# Drifter.net
KiCad netlist of a schematic drawn in EAGLE
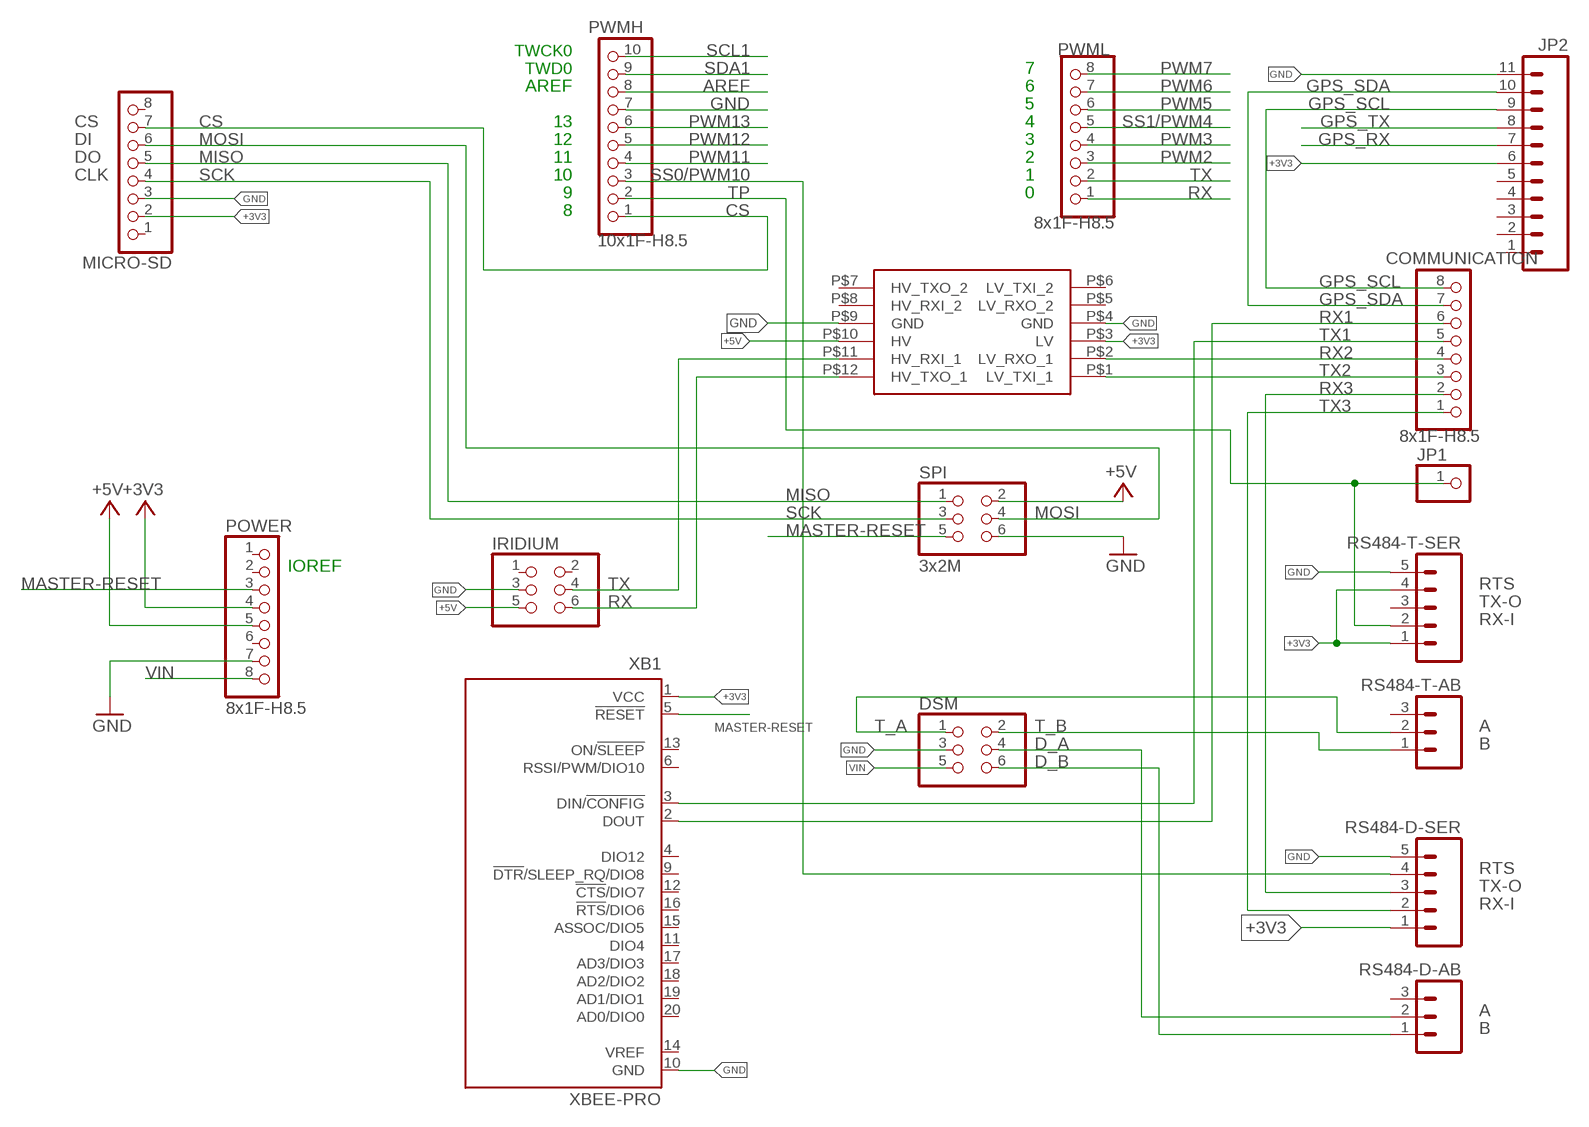
[diagram p0: schematic, sheet 1]

(export (version "E")
  (design (tool "Eeschema 10.0.6"))
  (components
    (comp (ref "COMMUNICATION")
      (value "8x1F-H8.5")
      (footprint "eagle-import:1X08")
      (libsource (lib "eagle-import") (part "PINHD-1X8"))
    )
    (comp (ref "DSM")
      (value "PINHD-2X3")
      (footprint "eagle-import:2X03")
      (libsource (lib "eagle-import") (part "pinhead_PINHD-2X3"))
    )
    (comp (ref "IRIDIUM")
      (value "PINHD-2X3")
      (footprint "eagle-import:2X03")
      (libsource (lib "eagle-import") (part "pinhead_PINHD-2X3"))
    )
    (comp (ref "JP1")
      (value "PINHD-1X1")
      (footprint "eagle-import:1X01")
      (libsource (lib "eagle-import") (part "PINHD-1X1"))
    )
    (comp (ref "JP2")
      (value "M111.27MM")
      (footprint "eagle-import:1X11-1.27MM")
      (libsource (lib "eagle-import") (part "M111.27MM"))
    )
    (comp (ref "MICRO-SD")
      (value "PINHD-1X8BIG")
      (footprint "eagle-import:1X08-BIG")
      (libsource (lib "eagle-import") (part "PINHD-1X8BIG"))
    )
    (comp (ref "POWER")
      (value "8x1F-H8.5")
      (footprint "eagle-import:1X08")
      (libsource (lib "eagle-import") (part "PINHD-1X8"))
    )
    (comp (ref "PWMH")
      (value "10x1F-H8.5")
      (footprint "eagle-import:1X10")
      (libsource (lib "eagle-import") (part "PINHD-1X10"))
    )
    (comp (ref "PWML")
      (value "8x1F-H8.5")
      (footprint "eagle-import:1X08")
      (libsource (lib "eagle-import") (part "PINHD-1X8"))
    )
    (comp (ref "RS484-D-AB")
      (value "M03PTH")
      (footprint "eagle-import:1X03")
      (libsource (lib "eagle-import") (part "M03PTH"))
    )
    (comp (ref "RS484-D-SER")
      (value "M05PTH")
      (footprint "eagle-import:1X05")
      (libsource (lib "eagle-import") (part "M05PTH"))
    )
    (comp (ref "RS484-T-AB")
      (value "M03PTH")
      (footprint "eagle-import:1X03")
      (libsource (lib "eagle-import") (part "M03PTH"))
    )
    (comp (ref "RS484-T-SER")
      (value "M05PTH")
      (footprint "eagle-import:1X05")
      (libsource (lib "eagle-import") (part "M05PTH"))
    )
    (comp (ref "SPI")
      (value "3x2M")
      (footprint "eagle-import:2X03")
      (libsource (lib "eagle-import") (part "PINHD-2X3"))
    )
    (comp (ref "U$1")
      (value "LOGIC_LEVEL_CONVERTER")
      (footprint "eagle-import:LOGIC_LEVEL_CONVERTER")
      (libsource (lib "eagle-import") (part "LOGIC_LEVEL_CONVERTER"))
    )
    (comp (ref "XB1")
      (value "XBEE-PRO")
      (footprint "eagle-import:XBEE-PRO")
      (fields (field (name "MPN") "XBP24-AWI-001"))
      (libsource (lib "eagle-import") (part "XBEE-PRO"))
    )
  )
  (nets
    (net (code "1") (name "+3V3") (class "Default")
      (node (ref "JP2") (pin "6") (pinfunction "6_6") (pintype "passive"))
      (node (ref "MICRO-SD") (pin "2") (pinfunction "2_2") (pintype "passive"))
      (node (ref "POWER") (pin "4") (pinfunction "4_4") (pintype "passive"))
      (node (ref "RS484-D-SER") (pin "1") (pinfunction "1_1") (pintype "passive"))
      (node (ref "RS484-T-SER") (pin "1") (pinfunction "1_1") (pintype "passive"))
      (node (ref "RS484-T-SER") (pin "4") (pinfunction "4_4") (pintype "passive"))
      (node (ref "U$1") (pin "P$3") (pinfunction "LV_P$3") (pintype "bidirectional"))
      (node (ref "XB1") (pin "1") (pinfunction "VCC_1") (pintype "power_in"))
    )
    (net (code "2") (name "+5V") (class "Default")
      (node (ref "IRIDIUM") (pin "5") (pinfunction "5_5") (pintype "passive"))
      (node (ref "POWER") (pin "5") (pinfunction "5_5") (pintype "passive"))
      (node (ref "SPI") (pin "2") (pinfunction "2_2") (pintype "passive"))
      (node (ref "U$1") (pin "P$10") (pinfunction "HV_P$10") (pintype "bidirectional"))
    )
    (net (code "3") (name "/AREF") (class "Default")
      (node (ref "PWMH") (pin "8") (pinfunction "8_8") (pintype "passive"))
    )
    (net (code "4") (name "/CS") (class "Default")
      (node (ref "MICRO-SD") (pin "7") (pinfunction "7_7") (pintype "passive"))
      (node (ref "PWMH") (pin "1") (pinfunction "1_1") (pintype "passive"))
    )
    (net (code "5") (name "/D_A") (class "Default")
      (node (ref "DSM") (pin "4") (pinfunction "4_4") (pintype "passive"))
      (node (ref "RS484-D-AB") (pin "2") (pinfunction "2_2") (pintype "passive"))
    )
    (net (code "6") (name "/D_B") (class "Default")
      (node (ref "DSM") (pin "6") (pinfunction "6_6") (pintype "passive"))
      (node (ref "RS484-D-AB") (pin "1") (pinfunction "1_1") (pintype "passive"))
    )
    (net (code "7") (name "/GPS_RX") (class "Default")
      (node (ref "JP2") (pin "7") (pinfunction "7_7") (pintype "passive"))
    )
    (net (code "8") (name "/GPS_SCL") (class "Default")
      (node (ref "COMMUNICATION") (pin "8") (pinfunction "8_8") (pintype "passive"))
      (node (ref "JP2") (pin "9") (pinfunction "9_9") (pintype "passive"))
    )
    (net (code "9") (name "/GPS_SDA") (class "Default")
      (node (ref "COMMUNICATION") (pin "7") (pinfunction "7_7") (pintype "passive"))
      (node (ref "JP2") (pin "10") (pinfunction "10_10") (pintype "passive"))
    )
    (net (code "10") (name "/GPS_TX") (class "Default")
      (node (ref "JP2") (pin "8") (pinfunction "8_8") (pintype "passive"))
    )
    (net (code "11") (name "/MASTER-RESET") (class "Default")
      (node (ref "POWER") (pin "3") (pinfunction "3_3") (pintype "passive"))
      (node (ref "SPI") (pin "5") (pinfunction "5_5") (pintype "passive"))
      (node (ref "XB1") (pin "5") (pinfunction "~{RESET}_5") (pintype "input"))
    )
    (net (code "12") (name "/MISO") (class "Default")
      (node (ref "MICRO-SD") (pin "5") (pinfunction "5_5") (pintype "passive"))
      (node (ref "SPI") (pin "1") (pinfunction "1_1") (pintype "passive"))
    )
    (net (code "13") (name "/MOSI") (class "Default")
      (node (ref "MICRO-SD") (pin "6") (pinfunction "6_6") (pintype "passive"))
      (node (ref "SPI") (pin "4") (pinfunction "4_4") (pintype "passive"))
    )
    (net (code "14") (name "/PWM2") (class "Default")
      (node (ref "PWML") (pin "3") (pinfunction "3_3") (pintype "passive"))
    )
    (net (code "15") (name "/PWM3") (class "Default")
      (node (ref "PWML") (pin "4") (pinfunction "4_4") (pintype "passive"))
    )
    (net (code "16") (name "/PWM5") (class "Default")
      (node (ref "PWML") (pin "6") (pinfunction "6_6") (pintype "passive"))
    )
    (net (code "17") (name "/PWM6") (class "Default")
      (node (ref "PWML") (pin "7") (pinfunction "7_7") (pintype "passive"))
    )
    (net (code "18") (name "/PWM7") (class "Default")
      (node (ref "PWML") (pin "8") (pinfunction "8_8") (pintype "passive"))
    )
    (net (code "19") (name "/PWM11") (class "Default")
      (node (ref "PWMH") (pin "4") (pinfunction "4_4") (pintype "passive"))
    )
    (net (code "20") (name "/PWM12") (class "Default")
      (node (ref "PWMH") (pin "5") (pinfunction "5_5") (pintype "passive"))
    )
    (net (code "21") (name "/PWM13") (class "Default")
      (node (ref "PWMH") (pin "6") (pinfunction "6_6") (pintype "passive"))
    )
    (net (code "22") (name "/RX") (class "Default")
      (node (ref "PWML") (pin "1") (pinfunction "1_1") (pintype "passive"))
    )
    (net (code "23") (name "/RX1") (class "Default")
      (node (ref "COMMUNICATION") (pin "6") (pinfunction "6_6") (pintype "passive"))
      (node (ref "XB1") (pin "2") (pinfunction "DOUT_2") (pintype "output"))
    )
    (net (code "24") (name "/RX2") (class "Default")
      (node (ref "COMMUNICATION") (pin "4") (pinfunction "4_4") (pintype "passive"))
      (node (ref "U$1") (pin "P$2") (pinfunction "LV_RXO_1_P$2") (pintype "bidirectional"))
    )
    (net (code "25") (name "/RX3") (class "Default")
      (node (ref "COMMUNICATION") (pin "2") (pinfunction "2_2") (pintype "passive"))
      (node (ref "RS484-D-SER") (pin "3") (pinfunction "3_3") (pintype "passive"))
    )
    (net (code "26") (name "/SCK") (class "Default")
      (node (ref "MICRO-SD") (pin "4") (pinfunction "4_4") (pintype "passive"))
      (node (ref "SPI") (pin "3") (pinfunction "3_3") (pintype "passive"))
    )
    (net (code "27") (name "/SCL1") (class "Default")
      (node (ref "PWMH") (pin "10") (pinfunction "10_10") (pintype "passive"))
    )
    (net (code "28") (name "/SDA1") (class "Default")
      (node (ref "PWMH") (pin "9") (pinfunction "9_9") (pintype "passive"))
    )
    (net (code "29") (name "/SS0{slash}PWM10") (class "Default")
      (node (ref "PWMH") (pin "3") (pinfunction "3_3") (pintype "passive"))
      (node (ref "RS484-D-SER") (pin "4") (pinfunction "4_4") (pintype "passive"))
    )
    (net (code "30") (name "/SS1{slash}PWM4") (class "Default")
      (node (ref "PWML") (pin "5") (pinfunction "5_5") (pintype "passive"))
    )
    (net (code "31") (name "/TP") (class "Default")
      (node (ref "JP1") (pin "1") (pinfunction "1_1") (pintype "passive"))
      (node (ref "PWMH") (pin "2") (pinfunction "2_2") (pintype "passive"))
      (node (ref "RS484-T-SER") (pin "2") (pinfunction "2_2") (pintype "passive"))
    )
    (net (code "32") (name "/TX") (class "Default")
      (node (ref "PWML") (pin "2") (pinfunction "2_2") (pintype "passive"))
    )
    (net (code "33") (name "/TX1") (class "Default")
      (node (ref "COMMUNICATION") (pin "5") (pinfunction "5_5") (pintype "passive"))
      (node (ref "XB1") (pin "3") (pinfunction "DIN/~{CONFIG}_3") (pintype "input"))
    )
    (net (code "34") (name "/TX2") (class "Default")
      (node (ref "COMMUNICATION") (pin "3") (pinfunction "3_3") (pintype "passive"))
      (node (ref "U$1") (pin "P$1") (pinfunction "LV_TXI_1_P$1") (pintype "bidirectional"))
    )
    (net (code "35") (name "/TX3") (class "Default")
      (node (ref "COMMUNICATION") (pin "1") (pinfunction "1_1") (pintype "passive"))
      (node (ref "RS484-D-SER") (pin "2") (pinfunction "2_2") (pintype "passive"))
    )
    (net (code "36") (name "/T_A") (class "Default")
      (node (ref "DSM") (pin "1") (pinfunction "1_1") (pintype "passive"))
      (node (ref "RS484-T-AB") (pin "2") (pinfunction "2_2") (pintype "passive"))
    )
    (net (code "37") (name "/T_B") (class "Default")
      (node (ref "DSM") (pin "2") (pinfunction "2_2") (pintype "passive"))
      (node (ref "RS484-T-AB") (pin "1") (pinfunction "1_1") (pintype "passive"))
    )
    (net (code "38") (name "GND") (class "Default")
      (node (ref "DSM") (pin "3") (pinfunction "3_3") (pintype "passive"))
      (node (ref "IRIDIUM") (pin "3") (pinfunction "3_3") (pintype "passive"))
      (node (ref "JP2") (pin "11") (pinfunction "11_11") (pintype "passive"))
      (node (ref "MICRO-SD") (pin "3") (pinfunction "3_3") (pintype "passive"))
      (node (ref "POWER") (pin "7") (pinfunction "7_7") (pintype "passive"))
      (node (ref "PWMH") (pin "7") (pinfunction "7_7") (pintype "passive"))
      (node (ref "RS484-D-SER") (pin "5") (pinfunction "5_5") (pintype "passive"))
      (node (ref "RS484-T-SER") (pin "5") (pinfunction "5_5") (pintype "passive"))
      (node (ref "SPI") (pin "6") (pinfunction "6_6") (pintype "passive"))
      (node (ref "U$1") (pin "P$4") (pinfunction "GND_P$4") (pintype "bidirectional"))
      (node (ref "U$1") (pin "P$9") (pinfunction "GND_P$9") (pintype "bidirectional"))
      (node (ref "XB1") (pin "10") (pinfunction "GND_10") (pintype "power_in"))
    )
    (net (code "39") (name "Net-(U$1-HV_RXI_1)") (class "Default")
      (node (ref "IRIDIUM") (pin "4") (pinfunction "4_4") (pintype "passive"))
      (node (ref "U$1") (pin "P$11") (pinfunction "HV_RXI_1_P$11") (pintype "bidirectional"))
    )
    (net (code "40") (name "Net-(U$1-HV_TXO_1)") (class "Default")
      (node (ref "IRIDIUM") (pin "6") (pinfunction "6_6") (pintype "passive"))
      (node (ref "U$1") (pin "P$12") (pinfunction "HV_TXO_1_P$12") (pintype "bidirectional"))
    )
    (net (code "41") (name "VIN") (class "Default")
      (node (ref "DSM") (pin "5") (pinfunction "5_5") (pintype "passive"))
      (node (ref "POWER") (pin "8") (pinfunction "8_8") (pintype "passive"))
    )
    (net (code "42") (name "unconnected-(IRIDIUM-Pad1)") (class "Default")
      (node (ref "IRIDIUM") (pin "1") (pinfunction "1_1") (pintype "passive"))
    )
    (net (code "43") (name "unconnected-(IRIDIUM-Pad2)") (class "Default")
      (node (ref "IRIDIUM") (pin "2") (pinfunction "2_2") (pintype "passive"))
    )
    (net (code "44") (name "unconnected-(JP2-Pad1)") (class "Default")
      (node (ref "JP2") (pin "1") (pinfunction "1_1") (pintype "passive"))
    )
    (net (code "45") (name "unconnected-(JP2-Pad2)") (class "Default")
      (node (ref "JP2") (pin "2") (pinfunction "2_2") (pintype "passive"))
    )
    (net (code "46") (name "unconnected-(JP2-Pad3)") (class "Default")
      (node (ref "JP2") (pin "3") (pinfunction "3_3") (pintype "passive"))
    )
    (net (code "47") (name "unconnected-(JP2-Pad4)") (class "Default")
      (node (ref "JP2") (pin "4") (pinfunction "4_4") (pintype "passive"))
    )
    (net (code "48") (name "unconnected-(JP2-Pad5)") (class "Default")
      (node (ref "JP2") (pin "5") (pinfunction "5_5") (pintype "passive"))
    )
    (net (code "49") (name "unconnected-(MICRO-SD-Pad1)") (class "Default")
      (node (ref "MICRO-SD") (pin "1") (pinfunction "1_1") (pintype "passive"))
    )
    (net (code "50") (name "unconnected-(MICRO-SD-Pad8)") (class "Default")
      (node (ref "MICRO-SD") (pin "8") (pinfunction "8_8") (pintype "passive"))
    )
    (net (code "51") (name "unconnected-(POWER-Pad1)") (class "Default")
      (node (ref "POWER") (pin "1") (pinfunction "1_1") (pintype "passive"))
    )
    (net (code "52") (name "unconnected-(POWER-Pad2)") (class "Default")
      (node (ref "POWER") (pin "2") (pinfunction "2_2") (pintype "passive"))
    )
    (net (code "53") (name "unconnected-(POWER-Pad6)") (class "Default")
      (node (ref "POWER") (pin "6") (pinfunction "6_6") (pintype "passive"))
    )
    (net (code "54") (name "unconnected-(RS484-D-AB-Pad3)") (class "Default")
      (node (ref "RS484-D-AB") (pin "3") (pinfunction "3_3") (pintype "passive"))
    )
    (net (code "55") (name "unconnected-(RS484-T-AB-Pad3)") (class "Default")
      (node (ref "RS484-T-AB") (pin "3") (pinfunction "3_3") (pintype "passive"))
    )
    (net (code "56") (name "unconnected-(RS484-T-SER-Pad3)") (class "Default")
      (node (ref "RS484-T-SER") (pin "3") (pinfunction "3_3") (pintype "passive"))
    )
    (net (code "57") (name "unconnected-(U$1-HV_RXI_2-PadP$8)") (class "Default")
      (node (ref "U$1") (pin "P$8") (pinfunction "HV_RXI_2_P$8") (pintype "bidirectional"))
    )
    (net (code "58") (name "unconnected-(U$1-HV_TXO_2-PadP$7)") (class "Default")
      (node (ref "U$1") (pin "P$7") (pinfunction "HV_TXO_2_P$7") (pintype "bidirectional"))
    )
    (net (code "59") (name "unconnected-(U$1-LV_RXO_2-PadP$5)") (class "Default")
      (node (ref "U$1") (pin "P$5") (pinfunction "LV_RXO_2_P$5") (pintype "bidirectional"))
    )
    (net (code "60") (name "unconnected-(U$1-LV_TXI_2-PadP$6)") (class "Default")
      (node (ref "U$1") (pin "P$6") (pinfunction "LV_TXI_2_P$6") (pintype "bidirectional"))
    )
    (net (code "61") (name "unconnected-(XB1-AD0{slash}DIO0-Pad20)") (class "Default")
      (node (ref "XB1") (pin "20") (pinfunction "AD0/DIO0_20") (pintype "bidirectional"))
    )
    (net (code "62") (name "unconnected-(XB1-AD1{slash}DIO1-Pad19)") (class "Default")
      (node (ref "XB1") (pin "19") (pinfunction "AD1/DIO1_19") (pintype "bidirectional"))
    )
    (net (code "63") (name "unconnected-(XB1-AD2{slash}DIO2-Pad18)") (class "Default")
      (node (ref "XB1") (pin "18") (pinfunction "AD2/DIO2_18") (pintype "bidirectional"))
    )
    (net (code "64") (name "unconnected-(XB1-AD3{slash}DIO3-Pad17)") (class "Default")
      (node (ref "XB1") (pin "17") (pinfunction "AD3/DIO3_17") (pintype "bidirectional"))
    )
    (net (code "65") (name "unconnected-(XB1-ASSOC{slash}DIO5-Pad15)") (class "Default")
      (node (ref "XB1") (pin "15") (pinfunction "ASSOC/DIO5_15") (pintype "bidirectional"))
    )
    (net (code "66") (name "unconnected-(XB1-DIO4-Pad11)") (class "Default")
      (node (ref "XB1") (pin "11") (pinfunction "DIO4_11") (pintype "bidirectional"))
    )
    (net (code "67") (name "unconnected-(XB1-DIO12-Pad4)") (class "Default")
      (node (ref "XB1") (pin "4") (pinfunction "DIO12_4") (pintype "bidirectional"))
    )
    (net (code "68") (name "unconnected-(XB1-ON{slash}~{SLEEP}-Pad13)") (class "Default")
      (node (ref "XB1") (pin "13") (pinfunction "ON/~{SLEEP}_13") (pintype "output"))
    )
    (net (code "69") (name "unconnected-(XB1-RSSI{slash}PWM{slash}DIO10-Pad6)") (class "Default")
      (node (ref "XB1") (pin "6") (pinfunction "RSSI/PWM/DIO10_6") (pintype "output"))
    )
    (net (code "70") (name "unconnected-(XB1-VREF-Pad14)") (class "Default")
      (node (ref "XB1") (pin "14") (pinfunction "VREF_14") (pintype "input"))
    )
    (net (code "71") (name "unconnected-(XB1-~{CTS}{slash}DIO7-Pad12)") (class "Default")
      (node (ref "XB1") (pin "12") (pinfunction "~{CTS}/DIO7_12") (pintype "bidirectional"))
    )
    (net (code "72") (name "unconnected-(XB1-~{DTR}{slash}SLEEP_RQ{slash}DIO8-Pad9)") (class "Default")
      (node (ref "XB1") (pin "9") (pinfunction "~{DTR}/SLEEP_RQ/DIO8_9") (pintype "bidirectional"))
    )
    (net (code "73") (name "unconnected-(XB1-~{RTS}{slash}DIO6-Pad16)") (class "Default")
      (node (ref "XB1") (pin "16") (pinfunction "~{RTS}/DIO6_16") (pintype "bidirectional"))
    )
  )
)
